# 2023-01-02_ESP32-Cseries_Riser_v1_1_w_US.net
KiCad netlist of a schematic drawn in EasyEDA
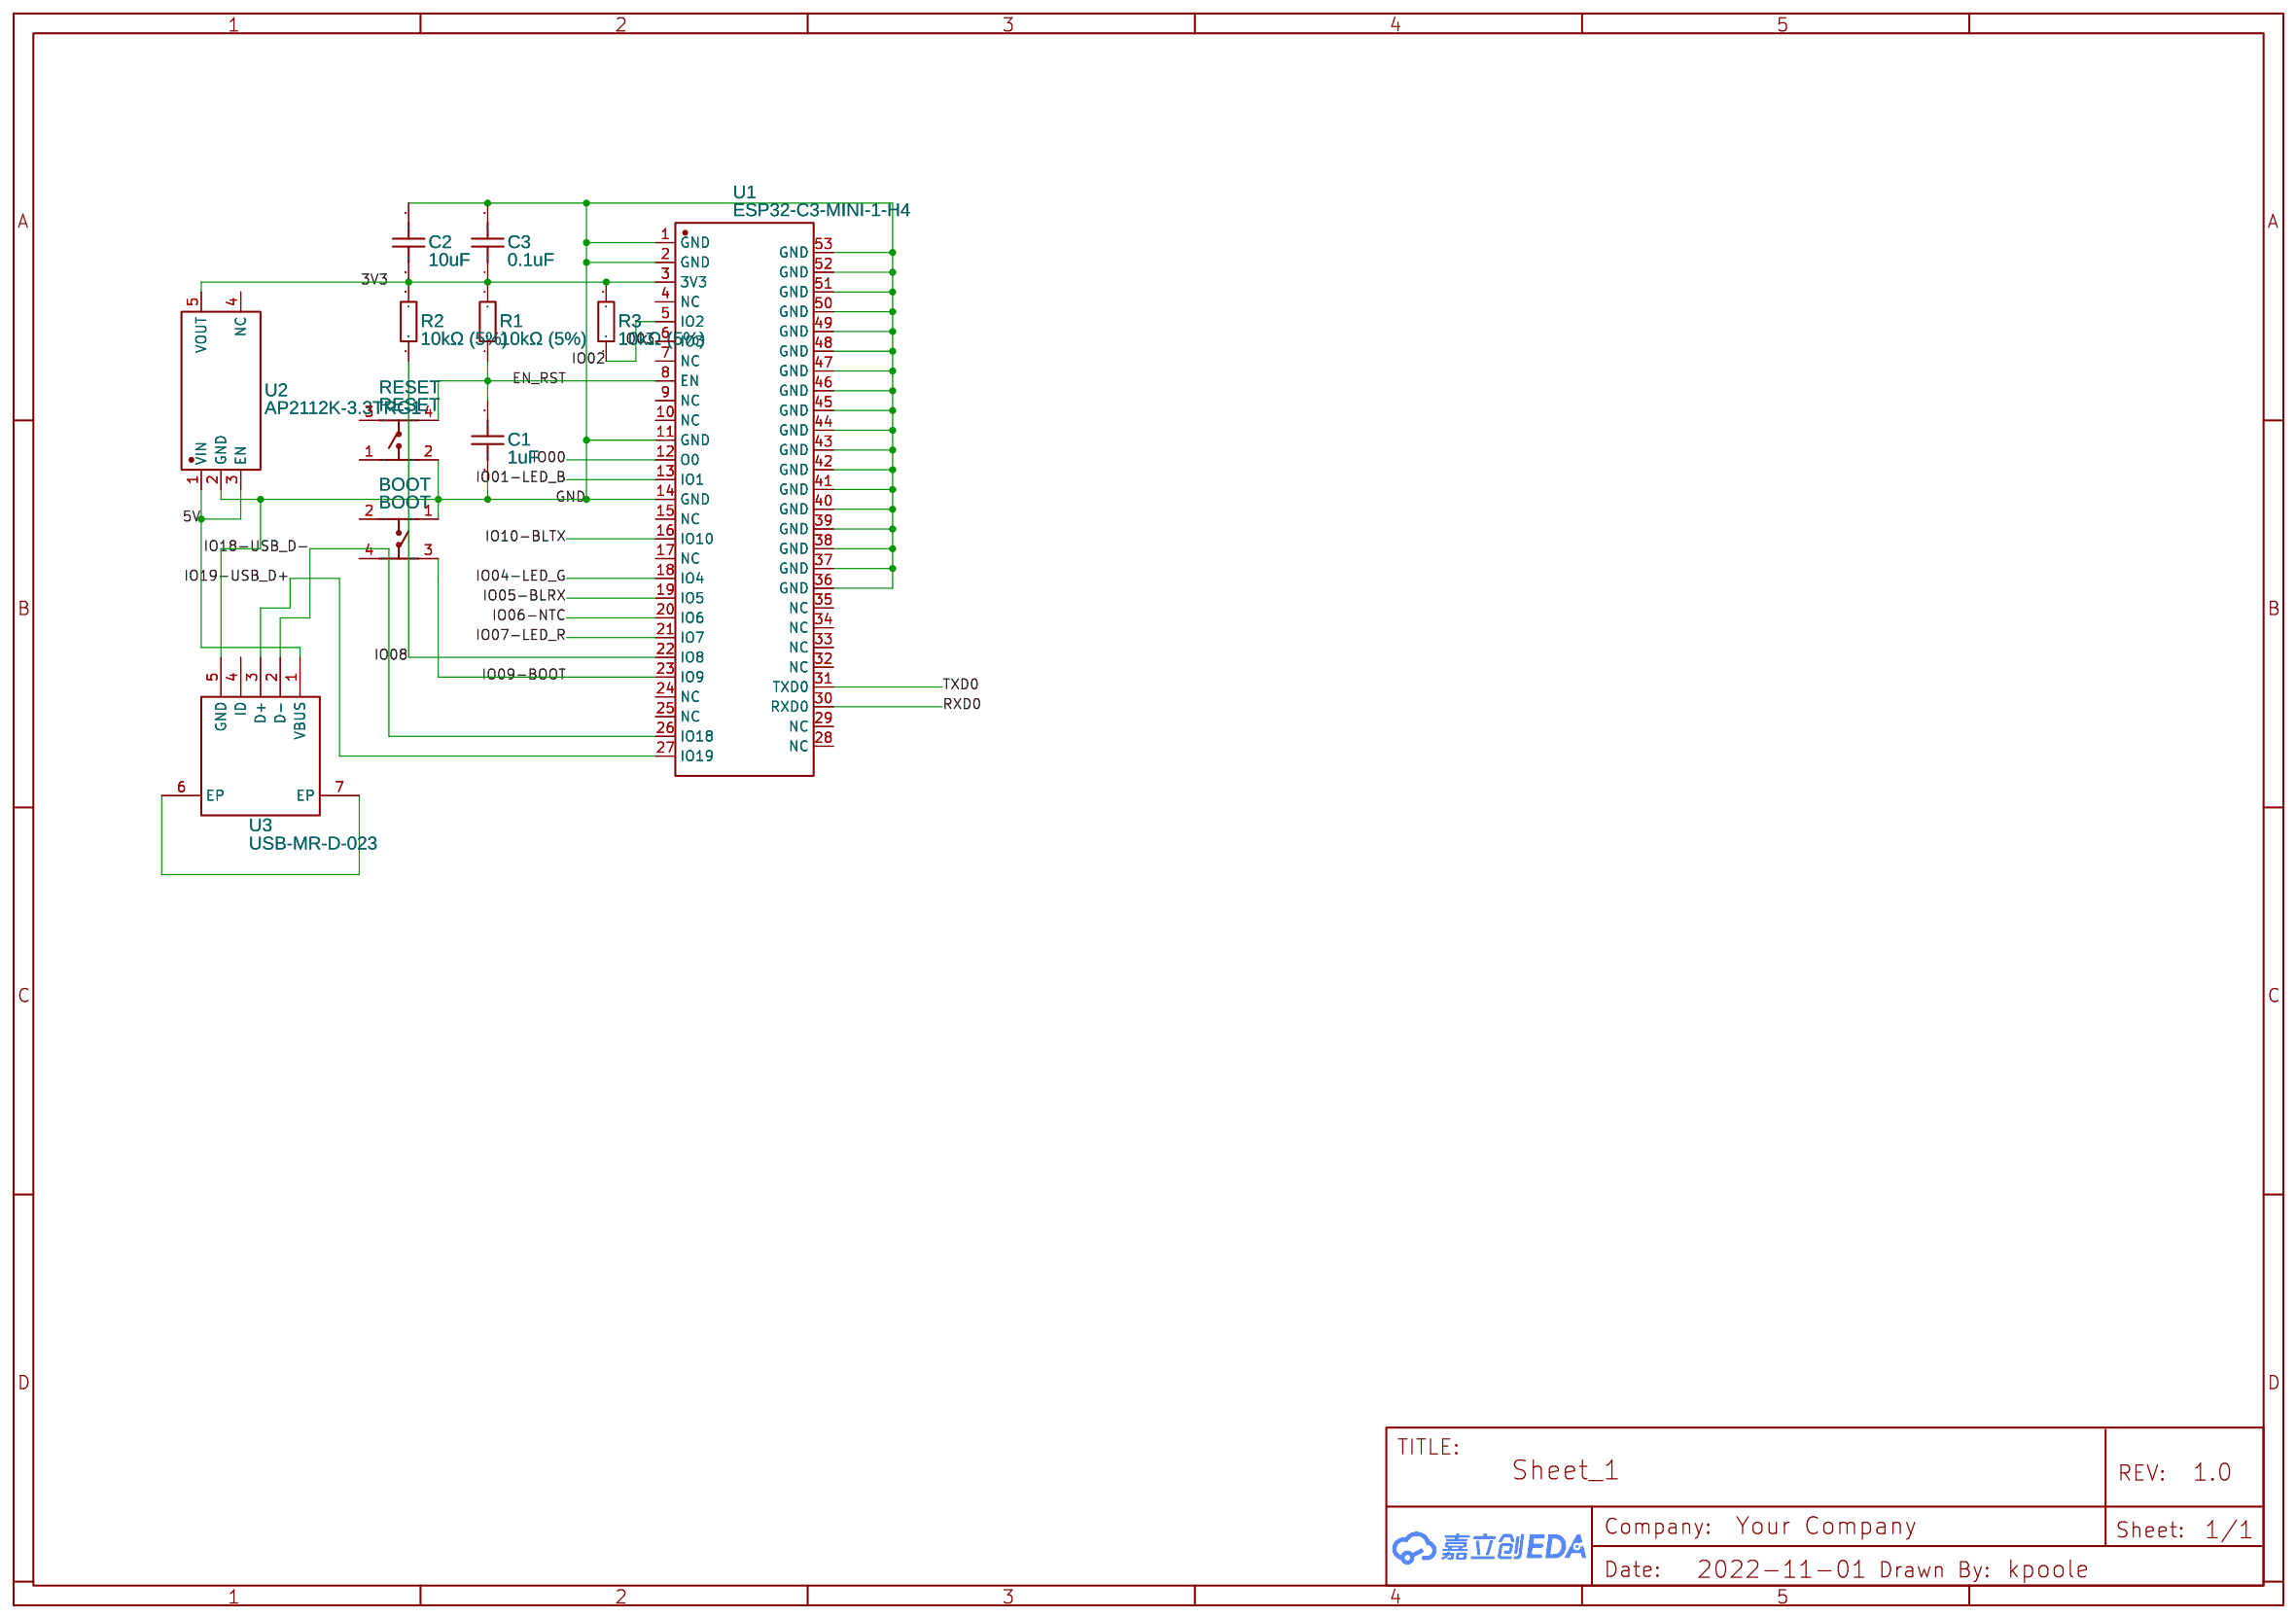
[diagram p0: schematic sheet]

(export (version "E")
  (design (tool "Eeschema 10.0.6"))
  (components
    (comp (ref "BOOT")
      (value "BOOT")
      (fields
        (field (name "BOM_Manufacturer Part") "1TS026A-1700-0553-CT")
        (field (name "BOM_Supplier Part") "C913785")
      )
      (libsource (lib "") (part "1TS026A-1700-0553-CT"))
    )
    (comp (ref "C1")
      (value "1uF")
      (fields
        (field (name "BOM_Manufacturer Part") "0603BB104K500NGT")
        (field (name "BOM_Supplier Part") "C2168571")
      )
      (libsource (lib "") (part "0603BB104K500NGT"))
    )
    (comp (ref "C2")
      (value "10uF")
      (fields
        (field (name "BOM_Manufacturer Part") "CL10A226MP8NUNE")
        (field (name "BOM_Supplier Part") "C86295")
      )
      (libsource (lib "") (part "CL10A226MP8NUNE"))
    )
    (comp (ref "C3")
      (value "0.1uF")
      (fields
        (field (name "BOM_Manufacturer Part") "CAP-SMD-0603-10uF-50V-10%")
        (field (name "BOM_Supplier Part") "C9900006127")
      )
      (libsource (lib "") (part "CAP-SMD-0603-10UF-50V-10%"))
    )
    (comp (ref "R1")
      (value "10kΩ (5%)")
      (fields
        (field (name "BOM_Manufacturer Part") "RK73B2ATTD103J")
        (field (name "BOM_Supplier Part") "C159912")
      )
      (libsource (lib "") (part "RK73B2ATTD103J"))
    )
    (comp (ref "R2")
      (value "10kΩ (5%)")
      (fields
        (field (name "BOM_Manufacturer Part") "RK73B2ATTD103J")
        (field (name "BOM_Supplier Part") "C159912")
      )
      (libsource (lib "") (part "RK73B2ATTD103J"))
    )
    (comp (ref "R3")
      (value "10kΩ (5%)")
      (fields
        (field (name "BOM_Manufacturer Part") "RK73B2ATTD103J")
        (field (name "BOM_Supplier Part") "C159912")
      )
      (libsource (lib "") (part "RK73B2ATTD103J"))
    )
    (comp (ref "RESET")
      (value "RESET")
      (fields
        (field (name "BOM_Manufacturer Part") "1TS026A-1700-0553-CT")
        (field (name "BOM_Supplier Part") "C913785")
      )
      (libsource (lib "") (part "1TS026A-1700-0553-CT_1"))
    )
    (comp (ref "U1")
      (value "ESP32-C3-MINI-1-H4")
      (fields (field (name "BOM_Supplier Part") "C2935306"))
      (libsource (lib "") (part "ESP32-C3-MINI-1-H4"))
    )
    (comp (ref "U2")
      (value "AP2112K-3.3TRG1")
      (fields (field (name "BOM_Supplier Part") "C51118"))
      (libsource (lib "") (part "AP2112K-3.3TRG1"))
    )
    (comp (ref "U3")
      (value "USB-MR-D-023")
      (fields (field (name "BOM_Supplier Part") "C2926994"))
      (libsource (lib "") (part "USB-MR-D-023"))
    )
  )
  (nets
    (net (code "1") (name "/3V3") (class "Default")
      (node (ref "C2") (pin "2") (pinfunction "2_2") (pintype "unspecified"))
      (node (ref "C3") (pin "1") (pinfunction "1_1") (pintype "unspecified"))
      (node (ref "R1") (pin "2") (pinfunction "2_2") (pintype "unspecified"))
      (node (ref "R2") (pin "2") (pinfunction "2_2") (pintype "unspecified"))
      (node (ref "R3") (pin "2") (pinfunction "2_2") (pintype "unspecified"))
      (node (ref "U1") (pin "3") (pinfunction "3V3_3") (pintype "unspecified"))
      (node (ref "U2") (pin "5") (pinfunction "VOUT_5") (pintype "unspecified"))
    )
    (net (code "2") (name "/5V") (class "Default")
      (node (ref "U2") (pin "1") (pinfunction "VIN_1") (pintype "unspecified"))
      (node (ref "U2") (pin "3") (pinfunction "EN_3") (pintype "unspecified"))
      (node (ref "U3") (pin "1") (pinfunction "VBUS_1") (pintype "unspecified"))
    )
    (net (code "3") (name "/EN_RST") (class "Default")
      (node (ref "C1") (pin "2") (pinfunction "2_2") (pintype "unspecified"))
      (node (ref "R1") (pin "1") (pinfunction "1_1") (pintype "unspecified"))
      (node (ref "RESET") (pin "4") (pinfunction "4_4") (pintype "unspecified"))
      (node (ref "U1") (pin "8") (pinfunction "EN_8") (pintype "unspecified"))
    )
    (net (code "4") (name "/GND") (class "Default")
      (node (ref "BOOT") (pin "1") (pinfunction "1_1") (pintype "unspecified"))
      (node (ref "C1") (pin "1") (pinfunction "1_1") (pintype "unspecified"))
      (node (ref "C2") (pin "1") (pinfunction "1_1") (pintype "unspecified"))
      (node (ref "C3") (pin "2") (pinfunction "2_2") (pintype "unspecified"))
      (node (ref "RESET") (pin "2") (pinfunction "2_2") (pintype "unspecified"))
      (node (ref "U1") (pin "1") (pinfunction "GND_1") (pintype "unspecified"))
      (node (ref "U1") (pin "11") (pinfunction "GND_11") (pintype "unspecified"))
      (node (ref "U1") (pin "14") (pinfunction "GND_14") (pintype "unspecified"))
      (node (ref "U1") (pin "2") (pinfunction "GND_2") (pintype "unspecified"))
      (node (ref "U1") (pin "36") (pinfunction "GND_36") (pintype "unspecified"))
      (node (ref "U1") (pin "37") (pinfunction "GND_37") (pintype "unspecified"))
      (node (ref "U1") (pin "38") (pinfunction "GND_38") (pintype "unspecified"))
      (node (ref "U1") (pin "39") (pinfunction "GND_39") (pintype "unspecified"))
      (node (ref "U1") (pin "40") (pinfunction "GND_40") (pintype "unspecified"))
      (node (ref "U1") (pin "41") (pinfunction "GND_41") (pintype "unspecified"))
      (node (ref "U1") (pin "42") (pinfunction "GND_42") (pintype "unspecified"))
      (node (ref "U1") (pin "43") (pinfunction "GND_43") (pintype "unspecified"))
      (node (ref "U1") (pin "44") (pinfunction "GND_44") (pintype "unspecified"))
      (node (ref "U1") (pin "45") (pinfunction "GND_45") (pintype "unspecified"))
      (node (ref "U1") (pin "46") (pinfunction "GND_46") (pintype "unspecified"))
      (node (ref "U1") (pin "47") (pinfunction "GND_47") (pintype "unspecified"))
      (node (ref "U1") (pin "48") (pinfunction "GND_48") (pintype "unspecified"))
      (node (ref "U1") (pin "49") (pinfunction "GND_49") (pintype "unspecified"))
      (node (ref "U1") (pin "50") (pinfunction "GND_50") (pintype "unspecified"))
      (node (ref "U1") (pin "51") (pinfunction "GND_51") (pintype "unspecified"))
      (node (ref "U1") (pin "52") (pinfunction "GND_52") (pintype "unspecified"))
      (node (ref "U1") (pin "53") (pinfunction "GND_53") (pintype "unspecified"))
      (node (ref "U2") (pin "2") (pinfunction "GND_2") (pintype "unspecified"))
      (node (ref "U3") (pin "5") (pinfunction "GND_5") (pintype "unspecified"))
    )
    (net (code "5") (name "/IO00") (class "Default")
      (node (ref "U1") (pin "12") (pinfunction "O0_12") (pintype "unspecified"))
    )
    (net (code "6") (name "/IO01-LED_B") (class "Default")
      (node (ref "U1") (pin "13") (pinfunction "IO1_13") (pintype "unspecified"))
    )
    (net (code "7") (name "/IO02") (class "Default")
      (node (ref "R3") (pin "1") (pinfunction "1_1") (pintype "unspecified"))
      (node (ref "U1") (pin "5") (pinfunction "IO2_5") (pintype "unspecified"))
    )
    (net (code "8") (name "/IO03") (class "Default")
      (node (ref "U1") (pin "6") (pinfunction "IO3_6") (pintype "unspecified"))
    )
    (net (code "9") (name "/IO04-LED_G") (class "Default")
      (node (ref "U1") (pin "18") (pinfunction "IO4_18") (pintype "unspecified"))
    )
    (net (code "10") (name "/IO05-BLRX") (class "Default")
      (node (ref "U1") (pin "19") (pinfunction "IO5_19") (pintype "unspecified"))
    )
    (net (code "11") (name "/IO06-NTC") (class "Default")
      (node (ref "U1") (pin "20") (pinfunction "IO6_20") (pintype "unspecified"))
    )
    (net (code "12") (name "/IO07-LED_R") (class "Default")
      (node (ref "U1") (pin "21") (pinfunction "IO7_21") (pintype "unspecified"))
    )
    (net (code "13") (name "/IO08") (class "Default")
      (node (ref "R2") (pin "1") (pinfunction "1_1") (pintype "unspecified"))
      (node (ref "U1") (pin "22") (pinfunction "IO8_22") (pintype "unspecified"))
    )
    (net (code "14") (name "/IO09-BOOT") (class "Default")
      (node (ref "BOOT") (pin "3") (pinfunction "3_3") (pintype "unspecified"))
      (node (ref "U1") (pin "23") (pinfunction "IO9_23") (pintype "unspecified"))
    )
    (net (code "15") (name "/IO10-BLTX") (class "Default")
      (node (ref "U1") (pin "16") (pinfunction "IO10_16") (pintype "unspecified"))
    )
    (net (code "16") (name "/IO18-USB_D-") (class "Default")
      (node (ref "U1") (pin "26") (pinfunction "IO18_26") (pintype "unspecified"))
      (node (ref "U3") (pin "2") (pinfunction "D-_2") (pintype "unspecified"))
    )
    (net (code "17") (name "/IO19-USB_D+") (class "Default")
      (node (ref "U1") (pin "27") (pinfunction "IO19_27") (pintype "unspecified"))
      (node (ref "U3") (pin "3") (pinfunction "D+_3") (pintype "unspecified"))
    )
    (net (code "18") (name "/RXD0") (class "Default")
      (node (ref "U1") (pin "30") (pinfunction "RXD0_30") (pintype "unspecified"))
    )
    (net (code "19") (name "/TXD0") (class "Default")
      (node (ref "U1") (pin "31") (pinfunction "TXD0_31") (pintype "unspecified"))
    )
    (net (code "20") (name "Net-(U3-EP-Pad6)") (class "Default")
      (node (ref "U3") (pin "6") (pinfunction "EP_6") (pintype "unspecified"))
      (node (ref "U3") (pin "7") (pinfunction "EP_7") (pintype "unspecified"))
    )
    (net (code "21") (name "unconnected-(BOOT-Pad2)") (class "Default")
      (node (ref "BOOT") (pin "2") (pinfunction "2_2") (pintype "unspecified"))
    )
    (net (code "22") (name "unconnected-(BOOT-Pad4)") (class "Default")
      (node (ref "BOOT") (pin "4") (pinfunction "4_4") (pintype "unspecified"))
    )
    (net (code "23") (name "unconnected-(RESET-Pad1)") (class "Default")
      (node (ref "RESET") (pin "1") (pinfunction "1_1") (pintype "unspecified"))
    )
    (net (code "24") (name "unconnected-(RESET-Pad3)") (class "Default")
      (node (ref "RESET") (pin "3") (pinfunction "3_3") (pintype "unspecified"))
    )
    (net (code "25") (name "unconnected-(U1-NC-Pad4)") (class "Default")
      (node (ref "U1") (pin "4") (pinfunction "NC_4") (pintype "unspecified"))
    )
    (net (code "26") (name "unconnected-(U1-NC-Pad7)") (class "Default")
      (node (ref "U1") (pin "7") (pinfunction "NC_7") (pintype "unspecified"))
    )
    (net (code "27") (name "unconnected-(U1-NC-Pad9)") (class "Default")
      (node (ref "U1") (pin "9") (pinfunction "NC_9") (pintype "unspecified"))
    )
    (net (code "28") (name "unconnected-(U1-NC-Pad10)") (class "Default")
      (node (ref "U1") (pin "10") (pinfunction "NC_10") (pintype "unspecified"))
    )
    (net (code "29") (name "unconnected-(U1-NC-Pad15)") (class "Default")
      (node (ref "U1") (pin "15") (pinfunction "NC_15") (pintype "unspecified"))
    )
    (net (code "30") (name "unconnected-(U1-NC-Pad17)") (class "Default")
      (node (ref "U1") (pin "17") (pinfunction "NC_17") (pintype "unspecified"))
    )
    (net (code "31") (name "unconnected-(U1-NC-Pad24)") (class "Default")
      (node (ref "U1") (pin "24") (pinfunction "NC_24") (pintype "unspecified"))
    )
    (net (code "32") (name "unconnected-(U1-NC-Pad25)") (class "Default")
      (node (ref "U1") (pin "25") (pinfunction "NC_25") (pintype "unspecified"))
    )
    (net (code "33") (name "unconnected-(U1-NC-Pad28)") (class "Default")
      (node (ref "U1") (pin "28") (pinfunction "NC_28") (pintype "unspecified"))
    )
    (net (code "34") (name "unconnected-(U1-NC-Pad29)") (class "Default")
      (node (ref "U1") (pin "29") (pinfunction "NC_29") (pintype "unspecified"))
    )
    (net (code "35") (name "unconnected-(U1-NC-Pad32)") (class "Default")
      (node (ref "U1") (pin "32") (pinfunction "NC_32") (pintype "unspecified"))
    )
    (net (code "36") (name "unconnected-(U1-NC-Pad33)") (class "Default")
      (node (ref "U1") (pin "33") (pinfunction "NC_33") (pintype "unspecified"))
    )
    (net (code "37") (name "unconnected-(U1-NC-Pad34)") (class "Default")
      (node (ref "U1") (pin "34") (pinfunction "NC_34") (pintype "unspecified"))
    )
    (net (code "38") (name "unconnected-(U1-NC-Pad35)") (class "Default")
      (node (ref "U1") (pin "35") (pinfunction "NC_35") (pintype "unspecified"))
    )
    (net (code "39") (name "unconnected-(U2-NC-Pad4)") (class "Default")
      (node (ref "U2") (pin "4") (pinfunction "NC_4") (pintype "unspecified"))
    )
    (net (code "40") (name "unconnected-(U3-ID-Pad4)") (class "Default")
      (node (ref "U3") (pin "4") (pinfunction "ID_4") (pintype "unspecified"))
    )
  )
)
